# MCU.net
KiCad netlist of a schematic drawn in Altium Designer
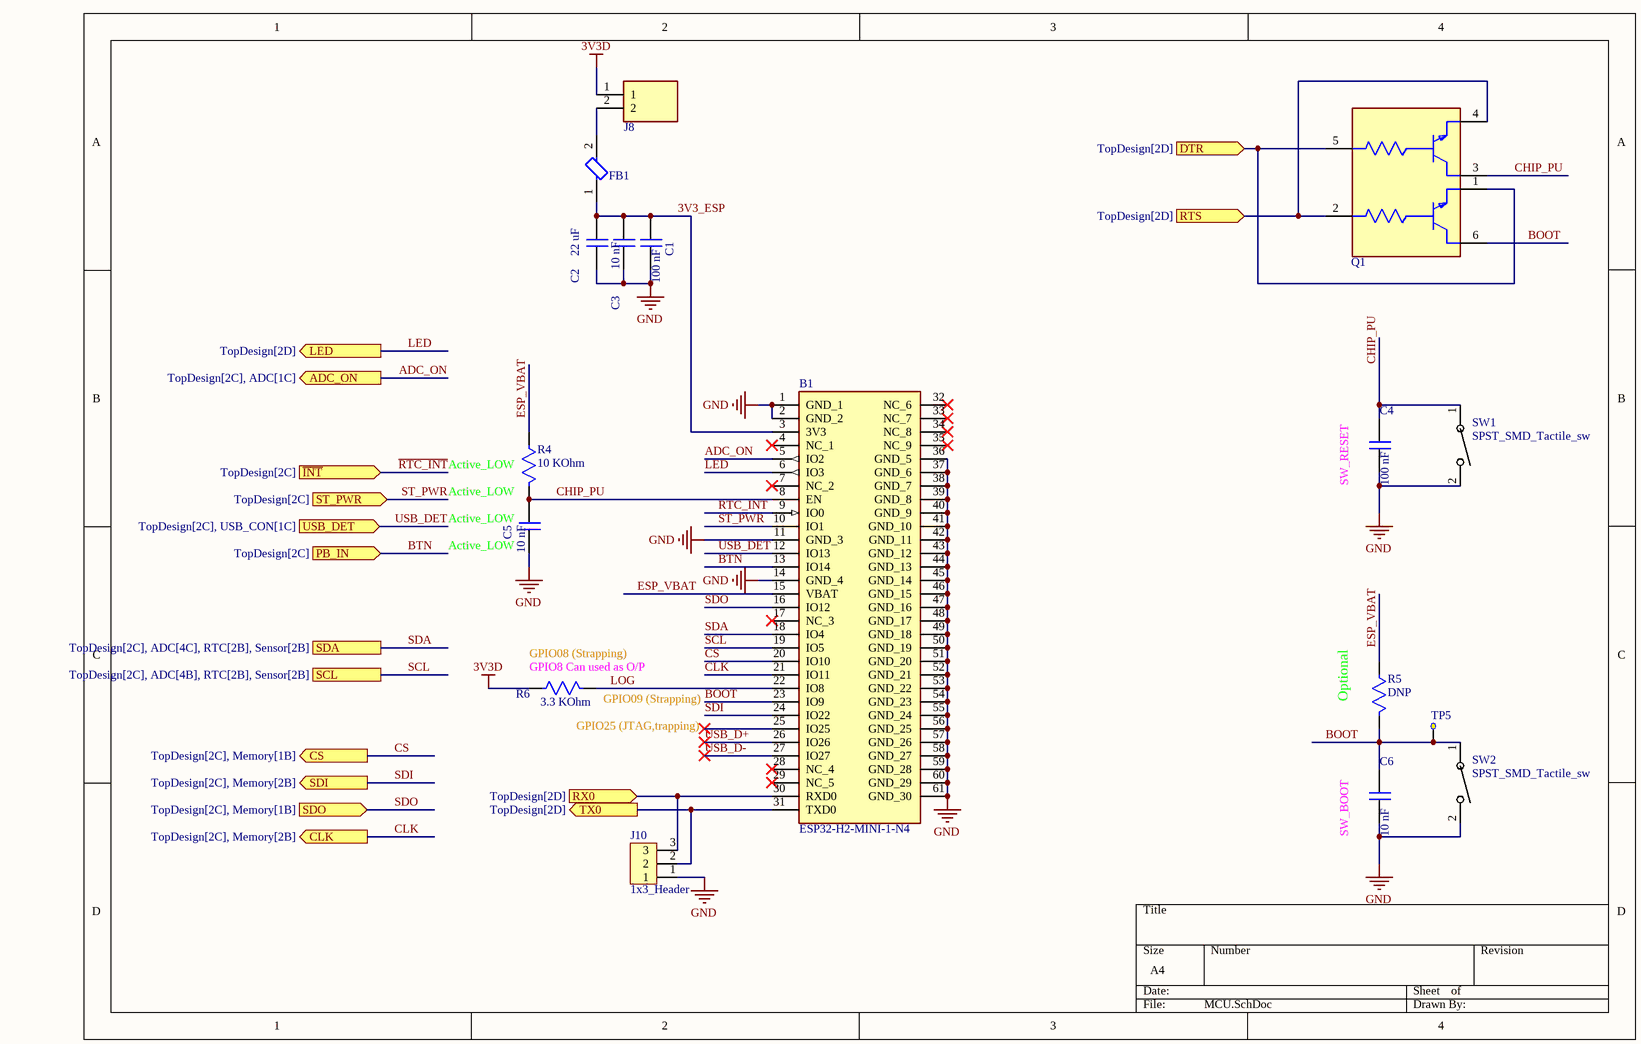
[diagram p0: MCU.SchDoc]

(export (version "E")
  (design (tool "Eeschema 10.0.6"))
  (components
    (comp (ref "B1")
      (value "ESP32-H2-MINI-1-N4")
      (footprint "ESP32-H2-MINI-1-NX")
      (libsource (lib "Aptinex_devices") (part "ESP32-H2-MINI-1-XX"))
    )
    (comp (ref "C1")
      (value "100 nF")
      (footprint "CAP_0603")
      (description "Cap SMD.")
      (libsource (lib "Aptinex_discrete") (part "Cap SMD"))
    )
    (comp (ref "C2")
      (value "22 uF")
      (footprint "CAP_0603")
      (description "Cap SMD.")
      (libsource (lib "Aptinex_discrete") (part "Cap SMD"))
    )
    (comp (ref "C3")
      (value "10 nF")
      (footprint "CAP_0603")
      (description "Cap SMD.")
      (libsource (lib "Aptinex_discrete") (part "Cap SMD"))
    )
    (comp (ref "C4")
      (value "100 nF")
      (footprint "CAP_0603")
      (description "Cap SMD.")
      (libsource (lib "Aptinex_discrete") (part "Cap SMD"))
    )
    (comp (ref "C5")
      (value "10 nF")
      (footprint "CAP_0603")
      (description "Cap SMD.")
      (libsource (lib "Aptinex_discrete") (part "Cap SMD"))
    )
    (comp (ref "C6")
      (value "10 nF")
      (footprint "CAP_0603")
      (description "Cap SMD.")
      (libsource (lib "Aptinex_discrete") (part "Cap SMD"))
    )
    (comp (ref "FB1")
      (value "BLM18KG601SN1D")
      (footprint "FBead_Murata_BLM18KG601SN1D")
      (libsource (lib "Aptinex_discrete") (part "BLM18KG601SN1D"))
    )
    (comp (ref "J8")
      (value "Pin_Header_2.54_2P")
      (footprint "Pin_Header_2.54_2P")
      (description "Pin_Header_2.54_2P_Straight")
      (fields (field (name "MANUFACTURER_PART_NUMBER") "61300211121"))
      (libsource (lib "Aptinex_connectors") (part "Pin_Header_2.54_2P"))
    )
    (comp (ref "J10")
      (value "1x3_Header")
      (footprint "1x3_Header")
      (libsource (lib "Aptinex_connectors") (part "1x3_Header"))
    )
    (comp (ref "Q1")
      (value "UMH3NTN-(Dual Transistor With Base Res)")
      (footprint "UMH3NTN-(Dual Transistor With Base Res-SOT-363)")
      (fields (field (name "MPN") "ROHM"))
      (libsource (lib "Aptinex_devices") (part "UMH3NTN-(Dual Transistor With Base Res)"))
    )
    (comp (ref "R4")
      (value "10 KOhm")
      (footprint "Res_0603")
      (description "SMD Resistor")
      (fields (field (name "MP") "RC0805FR-07330RL") (field (name "MF") "Yageo"))
      (libsource (lib "Aptinex_discrete") (part "Res smd"))
    )
    (comp (ref "R5")
      (value "DNP")
      (footprint "Res_0603")
      (description "SMD Resistor")
      (fields (field (name "MP") "RC0805FR-07330RL") (field (name "MF") "Yageo"))
      (libsource (lib "Aptinex_discrete") (part "Res smd"))
    )
    (comp (ref "R6")
      (value "3.3 KOhm")
      (footprint "Res_0603")
      (description "SMD Resistor")
      (fields (field (name "MP") "RC0805FR-07330RL") (field (name "MF") "Yageo"))
      (libsource (lib "Aptinex_discrete") (part "Res smd"))
    )
    (comp (ref "SW1")
      (value "SPST_SMD_Tactile_sw")
      (footprint "SPST_SMD_6mm")
      (description "SPST SMD Tactile Switches Rectangle button Brick nogging")
      (libsource (lib "Aptinex_discrete") (part "SPST_SMD_Tactile_sw"))
    )
    (comp (ref "SW2")
      (value "SPST_SMD_Tactile_sw")
      (footprint "SPST_SMD_6mm")
      (description "SPST SMD Tactile Switches Rectangle button Brick nogging")
      (libsource (lib "Aptinex_discrete") (part "SPST_SMD_Tactile_sw"))
    )
    (comp (ref "TP5")
      (value "boot")
      (footprint "Test_Point")
      (libsource (lib "Aptinex_discrete") (part "Test_Point"))
    )
  )
  (nets
    (net (code "1") (name "/3V3_ESP") (class "Default")
      (node (ref "B1") (pin "3") (pinfunction "3V3_3") (pintype "passive"))
      (node (ref "C1") (pin "2") (pinfunction "2_2") (pintype "passive"))
      (node (ref "C2") (pin "2") (pinfunction "2_2") (pintype "passive"))
      (node (ref "C3") (pin "2") (pinfunction "2_2") (pintype "passive"))
      (node (ref "FB1") (pin "1") (pinfunction "1_1") (pintype "passive"))
    )
    (net (code "2") (name "/ADC_ON") (class "Default")
      (node (ref "B1") (pin "5") (pinfunction "IO2_5") (pintype "output"))
    )
    (net (code "3") (name "/BOOT") (class "Default")
      (node (ref "B1") (pin "23") (pinfunction "IO9_23") (pintype "passive"))
      (node (ref "C6") (pin "2") (pinfunction "2_2") (pintype "passive"))
      (node (ref "Q1") (pin "6") (pinfunction "C_6") (pintype "passive"))
      (node (ref "R5") (pin "1") (pinfunction "1_1") (pintype "passive"))
      (node (ref "SW2") (pin "1") (pinfunction "1_1") (pintype "passive"))
      (node (ref "TP5") (pin "TP?") (pinfunction "Ref_Point_TP?") (pintype "passive"))
    )
    (net (code "4") (name "/BTN") (class "Default")
      (node (ref "B1") (pin "13") (pinfunction "IO14_13") (pintype "passive"))
    )
    (net (code "5") (name "/CHIP_PU") (class "Default")
      (node (ref "B1") (pin "8") (pinfunction "EN_8") (pintype "passive"))
      (node (ref "C4") (pin "2") (pinfunction "2_2") (pintype "passive"))
      (node (ref "C5") (pin "2") (pinfunction "2_2") (pintype "passive"))
      (node (ref "Q1") (pin "3") (pinfunction "C_3") (pintype "passive"))
      (node (ref "R4") (pin "1") (pinfunction "1_1") (pintype "passive"))
      (node (ref "SW1") (pin "1") (pinfunction "1_1") (pintype "passive"))
    )
    (net (code "6") (name "/CLK") (class "Default")
      (node (ref "B1") (pin "21") (pinfunction "IO11_21") (pintype "passive"))
    )
    (net (code "7") (name "/CS") (class "Default")
      (node (ref "B1") (pin "20") (pinfunction "IO10_20") (pintype "passive"))
    )
    (net (code "8") (name "/DTR") (class "Default")
      (node (ref "Q1") (pin "1") (pinfunction "E_1") (pintype "passive"))
      (node (ref "Q1") (pin "5") (pinfunction "B_5") (pintype "passive"))
    )
    (net (code "9") (name "/ESP_VBAT") (class "Default")
      (node (ref "B1") (pin "15") (pinfunction "VBAT_15") (pintype "passive"))
      (node (ref "R4") (pin "2") (pinfunction "2_2") (pintype "passive"))
      (node (ref "R5") (pin "2") (pinfunction "2_2") (pintype "passive"))
    )
    (net (code "10") (name "/LED") (class "Default")
      (node (ref "B1") (pin "6") (pinfunction "IO3_6") (pintype "output"))
    )
    (net (code "11") (name "/LOG") (class "Default")
      (node (ref "B1") (pin "22") (pinfunction "IO8_22") (pintype "passive"))
      (node (ref "R6") (pin "1") (pinfunction "1_1") (pintype "passive"))
    )
    (net (code "12") (name "/RTS") (class "Default")
      (node (ref "Q1") (pin "2") (pinfunction "B_2") (pintype "passive"))
      (node (ref "Q1") (pin "4") (pinfunction "E_4") (pintype "passive"))
    )
    (net (code "13") (name "/RX0") (class "Default")
      (node (ref "B1") (pin "30") (pinfunction "RXD0_30") (pintype "passive"))
      (node (ref "J10") (pin "3") (pinfunction "3_3") (pintype "passive"))
    )
    (net (code "14") (name "/SCL") (class "Default")
      (node (ref "B1") (pin "19") (pinfunction "IO5_19") (pintype "passive"))
    )
    (net (code "15") (name "/SDA") (class "Default")
      (node (ref "B1") (pin "18") (pinfunction "IO4_18") (pintype "passive"))
    )
    (net (code "16") (name "/SDI") (class "Default")
      (node (ref "B1") (pin "24") (pinfunction "IO22_24") (pintype "passive"))
    )
    (net (code "17") (name "/SDO") (class "Default")
      (node (ref "B1") (pin "16") (pinfunction "IO12_16") (pintype "passive"))
    )
    (net (code "18") (name "/ST_PWR") (class "Default")
      (node (ref "B1") (pin "10") (pinfunction "IO1_10") (pintype "passive"))
    )
    (net (code "19") (name "/TX0") (class "Default")
      (node (ref "B1") (pin "31") (pinfunction "TXD0_31") (pintype "passive"))
      (node (ref "J10") (pin "2") (pinfunction "2_2") (pintype "passive"))
    )
    (net (code "20") (name "/USB_D+") (class "Default")
      (node (ref "B1") (pin "26") (pinfunction "IO26_26") (pintype "passive+no_connect"))
    )
    (net (code "21") (name "/USB_D-") (class "Default")
      (node (ref "B1") (pin "27") (pinfunction "IO27_27") (pintype "passive+no_connect"))
    )
    (net (code "22") (name "/USB_DET") (class "Default")
      (node (ref "B1") (pin "12") (pinfunction "IO13_12") (pintype "passive"))
    )
    (net (code "23") (name "/~{RTC_INT}") (class "Default")
      (node (ref "B1") (pin "9") (pinfunction "IO0_9") (pintype "input"))
    )
    (net (code "24") (name "3V3D") (class "Default")
      (node (ref "J8") (pin "1") (pinfunction "1_1") (pintype "passive"))
      (node (ref "R6") (pin "2") (pinfunction "2_2") (pintype "passive"))
    )
    (net (code "25") (name "GND") (class "Default")
      (node (ref "B1") (pin "1") (pinfunction "GND_1_1") (pintype "passive"))
      (node (ref "B1") (pin "11") (pinfunction "GND_3_11") (pintype "passive"))
      (node (ref "B1") (pin "14") (pinfunction "GND_4_14") (pintype "passive"))
      (node (ref "B1") (pin "2") (pinfunction "GND_2_2") (pintype "passive"))
      (node (ref "B1") (pin "36") (pinfunction "GND_5_36") (pintype "passive"))
      (node (ref "B1") (pin "37") (pinfunction "GND_6_37") (pintype "passive"))
      (node (ref "B1") (pin "38") (pinfunction "GND_7_38") (pintype "passive"))
      (node (ref "B1") (pin "39") (pinfunction "GND_8_39") (pintype "passive"))
      (node (ref "B1") (pin "40") (pinfunction "GND_9_40") (pintype "passive"))
      (node (ref "B1") (pin "41") (pinfunction "GND_10_41") (pintype "passive"))
      (node (ref "B1") (pin "42") (pinfunction "GND_11_42") (pintype "passive"))
      (node (ref "B1") (pin "43") (pinfunction "GND_12_43") (pintype "passive"))
      (node (ref "B1") (pin "44") (pinfunction "GND_13_44") (pintype "passive"))
      (node (ref "B1") (pin "45") (pinfunction "GND_14_45") (pintype "passive"))
      (node (ref "B1") (pin "46") (pinfunction "GND_15_46") (pintype "passive"))
      (node (ref "B1") (pin "47") (pinfunction "GND_16_47") (pintype "passive"))
      (node (ref "B1") (pin "48") (pinfunction "GND_17_48") (pintype "passive"))
      (node (ref "B1") (pin "49") (pinfunction "GND_18_49") (pintype "passive"))
      (node (ref "B1") (pin "50") (pinfunction "GND_19_50") (pintype "passive"))
      (node (ref "B1") (pin "51") (pinfunction "GND_20_51") (pintype "passive"))
      (node (ref "B1") (pin "52") (pinfunction "GND_21_52") (pintype "passive"))
      (node (ref "B1") (pin "53") (pinfunction "GND_22_53") (pintype "passive"))
      (node (ref "B1") (pin "54") (pinfunction "GND_23_54") (pintype "passive"))
      (node (ref "B1") (pin "55") (pinfunction "GND_24_55") (pintype "passive"))
      (node (ref "B1") (pin "56") (pinfunction "GND_25_56") (pintype "passive"))
      (node (ref "B1") (pin "57") (pinfunction "GND_26_57") (pintype "passive"))
      (node (ref "B1") (pin "58") (pinfunction "GND_27_58") (pintype "passive"))
      (node (ref "B1") (pin "59") (pinfunction "GND_28_59") (pintype "passive"))
      (node (ref "B1") (pin "60") (pinfunction "GND_29_60") (pintype "passive"))
      (node (ref "B1") (pin "61") (pinfunction "GND_30_61") (pintype "passive"))
      (node (ref "C1") (pin "1") (pinfunction "1_1") (pintype "passive"))
      (node (ref "C2") (pin "1") (pinfunction "1_1") (pintype "passive"))
      (node (ref "C3") (pin "1") (pinfunction "1_1") (pintype "passive"))
      (node (ref "C4") (pin "1") (pinfunction "1_1") (pintype "passive"))
      (node (ref "C5") (pin "1") (pinfunction "1_1") (pintype "passive"))
      (node (ref "C6") (pin "1") (pinfunction "1_1") (pintype "passive"))
      (node (ref "J10") (pin "1") (pinfunction "1_1") (pintype "passive"))
      (node (ref "SW1") (pin "2") (pinfunction "2_2") (pintype "passive"))
      (node (ref "SW2") (pin "2") (pinfunction "2_2") (pintype "passive"))
    )
    (net (code "26") (name "Net-(FB1-Pad2)") (class "Default")
      (node (ref "FB1") (pin "2") (pinfunction "2_2") (pintype "passive"))
      (node (ref "J8") (pin "2") (pinfunction "2_2") (pintype "passive"))
    )
    (net (code "27") (name "unconnected-(B1-IO25-Pad25)") (class "Default")
      (node (ref "B1") (pin "25") (pinfunction "IO25_25") (pintype "passive+no_connect"))
    )
    (net (code "28") (name "unconnected-(B1-NC_1-Pad4)") (class "Default")
      (node (ref "B1") (pin "4") (pinfunction "NC_1_4") (pintype "passive+no_connect"))
    )
    (net (code "29") (name "unconnected-(B1-NC_2-Pad7)") (class "Default")
      (node (ref "B1") (pin "7") (pinfunction "NC_2_7") (pintype "passive+no_connect"))
    )
    (net (code "30") (name "unconnected-(B1-NC_3-Pad17)") (class "Default")
      (node (ref "B1") (pin "17") (pinfunction "NC_3_17") (pintype "passive+no_connect"))
    )
    (net (code "31") (name "unconnected-(B1-NC_4-Pad28)") (class "Default")
      (node (ref "B1") (pin "28") (pinfunction "NC_4_28") (pintype "passive+no_connect"))
    )
    (net (code "32") (name "unconnected-(B1-NC_5-Pad29)") (class "Default")
      (node (ref "B1") (pin "29") (pinfunction "NC_5_29") (pintype "passive+no_connect"))
    )
    (net (code "33") (name "unconnected-(B1-NC_6-Pad32)") (class "Default")
      (node (ref "B1") (pin "32") (pinfunction "NC_6_32") (pintype "passive+no_connect"))
    )
    (net (code "34") (name "unconnected-(B1-NC_7-Pad33)") (class "Default")
      (node (ref "B1") (pin "33") (pinfunction "NC_7_33") (pintype "passive+no_connect"))
    )
    (net (code "35") (name "unconnected-(B1-NC_8-Pad34)") (class "Default")
      (node (ref "B1") (pin "34") (pinfunction "NC_8_34") (pintype "passive+no_connect"))
    )
    (net (code "36") (name "unconnected-(B1-NC_9-Pad35)") (class "Default")
      (node (ref "B1") (pin "35") (pinfunction "NC_9_35") (pintype "passive+no_connect"))
    )
  )
)
